# CAPT-B1-01_Cap_Touch_Matrix_Shield.net
KiCad netlist of a schematic drawn in EAGLE
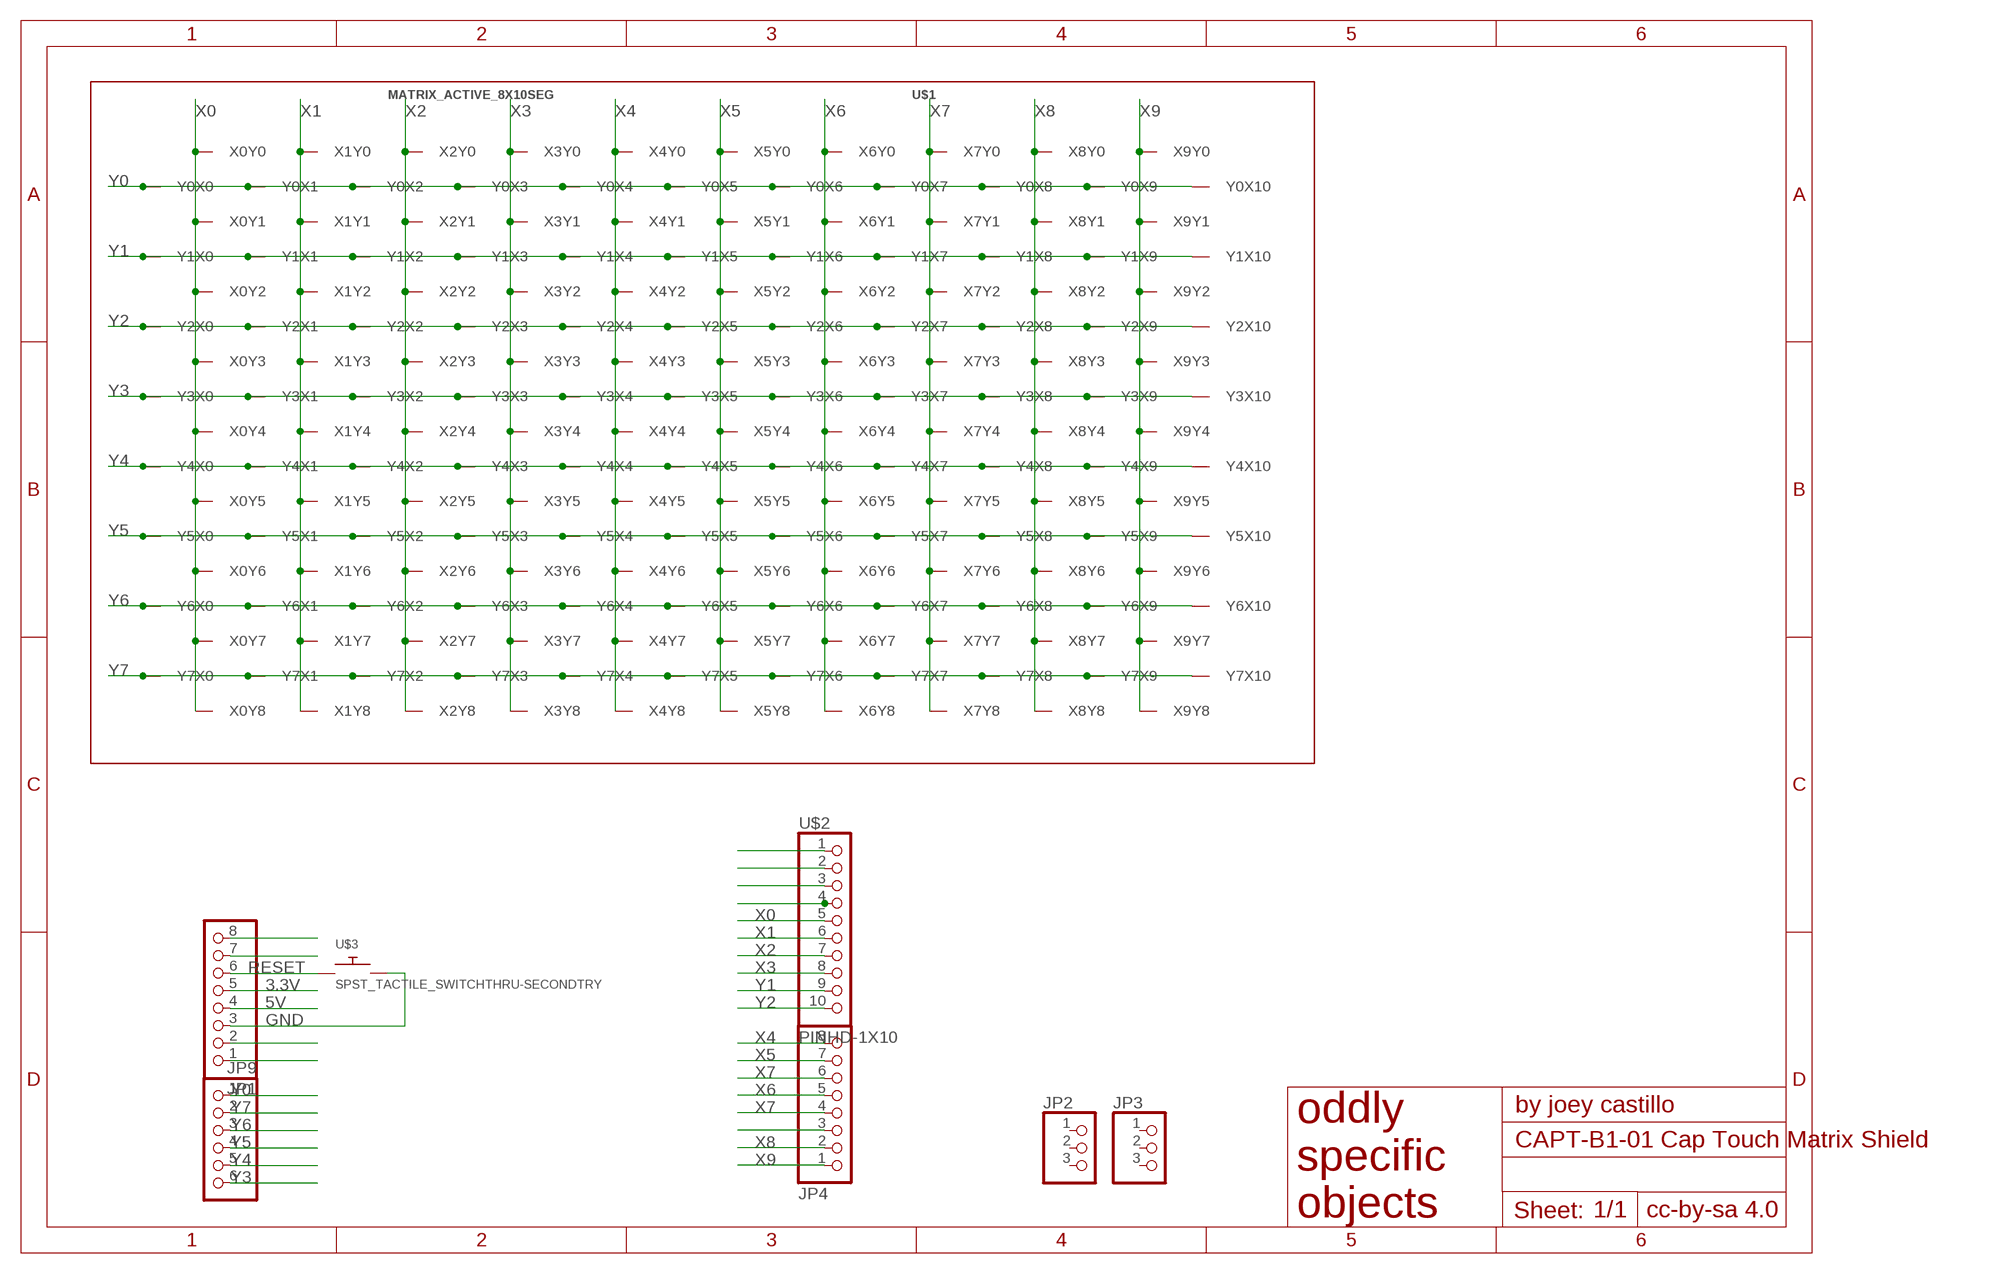
[diagram p0: schematic, sheet 1]

(export (version "E")
  (design (tool "Eeschema 10.0.6"))
  (components
    (comp (ref "JP1")
      (value "PINHD-1X8CLEANBIG")
      (footprint "eagle-import:1X08-CLEANBIG")
      (libsource (lib "eagle-import") (part "PINHD-1X8CLEANBIG"))
    )
    (comp (ref "JP2")
      (value "PINHD-1X3CB")
      (footprint "eagle-import:1X03-CLEANBIG")
      (libsource (lib "eagle-import") (part "PINHD-1X3CB"))
    )
    (comp (ref "JP3")
      (value "PINHD-1X3CB")
      (footprint "eagle-import:1X03-CLEANBIG")
      (libsource (lib "eagle-import") (part "PINHD-1X3CB"))
    )
    (comp (ref "JP4")
      (value "PINHD-1X8CLEANBIG")
      (footprint "eagle-import:1X08-CLEANBIG")
      (libsource (lib "eagle-import") (part "PINHD-1X8CLEANBIG"))
    )
    (comp (ref "JP9")
      (value "PINHD-1X6CB")
      (footprint "eagle-import:1X06-CLEANBIG")
      (libsource (lib "eagle-import") (part "PINHD-1X6CB"))
    )
    (comp (ref "U$1")
      (value "MATRIX_ACTIVE_8X10SEG")
      (footprint "eagle-import:MATRIX_ACTIVE_8X10SEG_4MM")
      (libsource (lib "eagle-import") (part "MATRIX_ACTIVE_8X10SEG"))
    )
    (comp (ref "U$2")
      (value "PINHD-1X10")
      (footprint "eagle-import:1X10-BIG")
      (libsource (lib "eagle-import") (part "PINHD-1X10"))
    )
    (comp (ref "U$3")
      (value "SPST_TACTILE_SWITCHTHRU-SECONDTRY")
      (footprint "eagle-import:MJTP1250-TRY2")
      (libsource (lib "eagle-import") (part "SPST_TACTILE_SWITCHTHRU-SECONDTRY"))
    )
  )
  (nets
    (net (code "1") (name "/3.3V") (class "Default")
      (node (ref "JP1") (pin "5") (pinfunction "5_5") (pintype "passive"))
    )
    (net (code "2") (name "/5V") (class "Default")
      (node (ref "JP1") (pin "4") (pinfunction "4_4") (pintype "passive"))
    )
    (net (code "3") (name "/GND") (class "Default")
      (node (ref "JP1") (pin "3") (pinfunction "3_3") (pintype "passive"))
      (node (ref "U$3") (pin "P$2") (pinfunction "P$2_P$2") (pintype "passive"))
    )
    (net (code "4") (name "/RESET") (class "Default")
      (node (ref "JP1") (pin "6") (pinfunction "6_6") (pintype "passive"))
      (node (ref "U$3") (pin "P$1") (pinfunction "P$1_P$1") (pintype "passive"))
    )
    (net (code "5") (name "/X0") (class "Default")
      (node (ref "U$1") (pin "X0Y0") (pinfunction "X0Y0_X0Y0") (pintype "passive"))
      (node (ref "U$1") (pin "X0Y1") (pinfunction "X0Y1_X0Y1") (pintype "passive"))
      (node (ref "U$1") (pin "X0Y2") (pinfunction "X0Y2_X0Y2") (pintype "passive"))
      (node (ref "U$1") (pin "X0Y3") (pinfunction "X0Y3_X0Y3") (pintype "passive"))
      (node (ref "U$1") (pin "X0Y4") (pinfunction "X0Y4_X0Y4") (pintype "passive"))
      (node (ref "U$1") (pin "X0Y5") (pinfunction "X0Y5_X0Y5") (pintype "passive"))
      (node (ref "U$1") (pin "X0Y6") (pinfunction "X0Y6_X0Y6") (pintype "passive"))
      (node (ref "U$1") (pin "X0Y7") (pinfunction "X0Y7_X0Y7") (pintype "passive"))
      (node (ref "U$1") (pin "X0Y8") (pinfunction "X0Y8_X0Y8") (pintype "passive"))
      (node (ref "U$2") (pin "5") (pinfunction "5_5") (pintype "passive"))
    )
    (net (code "6") (name "/X1") (class "Default")
      (node (ref "U$1") (pin "X1Y0") (pinfunction "X1Y0_X1Y0") (pintype "passive"))
      (node (ref "U$1") (pin "X1Y1") (pinfunction "X1Y1_X1Y1") (pintype "passive"))
      (node (ref "U$1") (pin "X1Y2") (pinfunction "X1Y2_X1Y2") (pintype "passive"))
      (node (ref "U$1") (pin "X1Y3") (pinfunction "X1Y3_X1Y3") (pintype "passive"))
      (node (ref "U$1") (pin "X1Y4") (pinfunction "X1Y4_X1Y4") (pintype "passive"))
      (node (ref "U$1") (pin "X1Y5") (pinfunction "X1Y5_X1Y5") (pintype "passive"))
      (node (ref "U$1") (pin "X1Y6") (pinfunction "X1Y6_X1Y6") (pintype "passive"))
      (node (ref "U$1") (pin "X1Y7") (pinfunction "X1Y7_X1Y7") (pintype "passive"))
      (node (ref "U$1") (pin "X1Y8") (pinfunction "X1Y8_X1Y8") (pintype "passive"))
      (node (ref "U$2") (pin "6") (pinfunction "6_6") (pintype "passive"))
    )
    (net (code "7") (name "/X2") (class "Default")
      (node (ref "U$1") (pin "X2Y0") (pinfunction "X2Y0_X2Y0") (pintype "passive"))
      (node (ref "U$1") (pin "X2Y1") (pinfunction "X2Y1_X2Y1") (pintype "passive"))
      (node (ref "U$1") (pin "X2Y2") (pinfunction "X2Y2_X2Y2") (pintype "passive"))
      (node (ref "U$1") (pin "X2Y3") (pinfunction "X2Y3_X2Y3") (pintype "passive"))
      (node (ref "U$1") (pin "X2Y4") (pinfunction "X2Y4_X2Y4") (pintype "passive"))
      (node (ref "U$1") (pin "X2Y5") (pinfunction "X2Y5_X2Y5") (pintype "passive"))
      (node (ref "U$1") (pin "X2Y6") (pinfunction "X2Y6_X2Y6") (pintype "passive"))
      (node (ref "U$1") (pin "X2Y7") (pinfunction "X2Y7_X2Y7") (pintype "passive"))
      (node (ref "U$1") (pin "X2Y8") (pinfunction "X2Y8_X2Y8") (pintype "passive"))
      (node (ref "U$2") (pin "7") (pinfunction "7_7") (pintype "passive"))
    )
    (net (code "8") (name "/X3") (class "Default")
      (node (ref "U$1") (pin "X3Y0") (pinfunction "X3Y0_X3Y0") (pintype "passive"))
      (node (ref "U$1") (pin "X3Y1") (pinfunction "X3Y1_X3Y1") (pintype "passive"))
      (node (ref "U$1") (pin "X3Y2") (pinfunction "X3Y2_X3Y2") (pintype "passive"))
      (node (ref "U$1") (pin "X3Y3") (pinfunction "X3Y3_X3Y3") (pintype "passive"))
      (node (ref "U$1") (pin "X3Y4") (pinfunction "X3Y4_X3Y4") (pintype "passive"))
      (node (ref "U$1") (pin "X3Y5") (pinfunction "X3Y5_X3Y5") (pintype "passive"))
      (node (ref "U$1") (pin "X3Y6") (pinfunction "X3Y6_X3Y6") (pintype "passive"))
      (node (ref "U$1") (pin "X3Y7") (pinfunction "X3Y7_X3Y7") (pintype "passive"))
      (node (ref "U$1") (pin "X3Y8") (pinfunction "X3Y8_X3Y8") (pintype "passive"))
      (node (ref "U$2") (pin "8") (pinfunction "8_8") (pintype "passive"))
    )
    (net (code "9") (name "/X4") (class "Default")
      (node (ref "JP4") (pin "8") (pinfunction "8_8") (pintype "passive"))
      (node (ref "U$1") (pin "X4Y0") (pinfunction "X4Y0_X4Y0") (pintype "passive"))
      (node (ref "U$1") (pin "X4Y1") (pinfunction "X4Y1_X4Y1") (pintype "passive"))
      (node (ref "U$1") (pin "X4Y2") (pinfunction "X4Y2_X4Y2") (pintype "passive"))
      (node (ref "U$1") (pin "X4Y3") (pinfunction "X4Y3_X4Y3") (pintype "passive"))
      (node (ref "U$1") (pin "X4Y4") (pinfunction "X4Y4_X4Y4") (pintype "passive"))
      (node (ref "U$1") (pin "X4Y5") (pinfunction "X4Y5_X4Y5") (pintype "passive"))
      (node (ref "U$1") (pin "X4Y6") (pinfunction "X4Y6_X4Y6") (pintype "passive"))
      (node (ref "U$1") (pin "X4Y7") (pinfunction "X4Y7_X4Y7") (pintype "passive"))
      (node (ref "U$1") (pin "X4Y8") (pinfunction "X4Y8_X4Y8") (pintype "passive"))
    )
    (net (code "10") (name "/X5") (class "Default")
      (node (ref "JP4") (pin "7") (pinfunction "7_7") (pintype "passive"))
      (node (ref "U$1") (pin "X5Y0") (pinfunction "X5Y0_X5Y0") (pintype "passive"))
      (node (ref "U$1") (pin "X5Y1") (pinfunction "X5Y1_X5Y1") (pintype "passive"))
      (node (ref "U$1") (pin "X5Y2") (pinfunction "X5Y2_X5Y2") (pintype "passive"))
      (node (ref "U$1") (pin "X5Y3") (pinfunction "X5Y3_X5Y3") (pintype "passive"))
      (node (ref "U$1") (pin "X5Y4") (pinfunction "X5Y4_X5Y4") (pintype "passive"))
      (node (ref "U$1") (pin "X5Y5") (pinfunction "X5Y5_X5Y5") (pintype "passive"))
      (node (ref "U$1") (pin "X5Y6") (pinfunction "X5Y6_X5Y6") (pintype "passive"))
      (node (ref "U$1") (pin "X5Y7") (pinfunction "X5Y7_X5Y7") (pintype "passive"))
      (node (ref "U$1") (pin "X5Y8") (pinfunction "X5Y8_X5Y8") (pintype "passive"))
    )
    (net (code "11") (name "/X6") (class "Default")
      (node (ref "JP4") (pin "5") (pinfunction "5_5") (pintype "passive"))
      (node (ref "U$1") (pin "X6Y0") (pinfunction "X6Y0_X6Y0") (pintype "passive"))
      (node (ref "U$1") (pin "X6Y1") (pinfunction "X6Y1_X6Y1") (pintype "passive"))
      (node (ref "U$1") (pin "X6Y2") (pinfunction "X6Y2_X6Y2") (pintype "passive"))
      (node (ref "U$1") (pin "X6Y3") (pinfunction "X6Y3_X6Y3") (pintype "passive"))
      (node (ref "U$1") (pin "X6Y4") (pinfunction "X6Y4_X6Y4") (pintype "passive"))
      (node (ref "U$1") (pin "X6Y5") (pinfunction "X6Y5_X6Y5") (pintype "passive"))
      (node (ref "U$1") (pin "X6Y6") (pinfunction "X6Y6_X6Y6") (pintype "passive"))
      (node (ref "U$1") (pin "X6Y7") (pinfunction "X6Y7_X6Y7") (pintype "passive"))
      (node (ref "U$1") (pin "X6Y8") (pinfunction "X6Y8_X6Y8") (pintype "passive"))
    )
    (net (code "12") (name "/X7") (class "Default")
      (node (ref "JP4") (pin "4") (pinfunction "4_4") (pintype "passive"))
      (node (ref "JP4") (pin "6") (pinfunction "6_6") (pintype "passive"))
      (node (ref "U$1") (pin "X7Y0") (pinfunction "X7Y0_X7Y0") (pintype "passive"))
      (node (ref "U$1") (pin "X7Y1") (pinfunction "X7Y1_X7Y1") (pintype "passive"))
      (node (ref "U$1") (pin "X7Y2") (pinfunction "X7Y2_X7Y2") (pintype "passive"))
      (node (ref "U$1") (pin "X7Y3") (pinfunction "X7Y3_X7Y3") (pintype "passive"))
      (node (ref "U$1") (pin "X7Y4") (pinfunction "X7Y4_X7Y4") (pintype "passive"))
      (node (ref "U$1") (pin "X7Y5") (pinfunction "X7Y5_X7Y5") (pintype "passive"))
      (node (ref "U$1") (pin "X7Y6") (pinfunction "X7Y6_X7Y6") (pintype "passive"))
      (node (ref "U$1") (pin "X7Y7") (pinfunction "X7Y7_X7Y7") (pintype "passive"))
      (node (ref "U$1") (pin "X7Y8") (pinfunction "X7Y8_X7Y8") (pintype "passive"))
    )
    (net (code "13") (name "/X8") (class "Default")
      (node (ref "JP4") (pin "2") (pinfunction "2_2") (pintype "passive"))
      (node (ref "U$1") (pin "X8Y0") (pinfunction "X8Y0_X8Y0") (pintype "passive"))
      (node (ref "U$1") (pin "X8Y1") (pinfunction "X8Y1_X8Y1") (pintype "passive"))
      (node (ref "U$1") (pin "X8Y2") (pinfunction "X8Y2_X8Y2") (pintype "passive"))
      (node (ref "U$1") (pin "X8Y3") (pinfunction "X8Y3_X8Y3") (pintype "passive"))
      (node (ref "U$1") (pin "X8Y4") (pinfunction "X8Y4_X8Y4") (pintype "passive"))
      (node (ref "U$1") (pin "X8Y5") (pinfunction "X8Y5_X8Y5") (pintype "passive"))
      (node (ref "U$1") (pin "X8Y6") (pinfunction "X8Y6_X8Y6") (pintype "passive"))
      (node (ref "U$1") (pin "X8Y7") (pinfunction "X8Y7_X8Y7") (pintype "passive"))
      (node (ref "U$1") (pin "X8Y8") (pinfunction "X8Y8_X8Y8") (pintype "passive"))
    )
    (net (code "14") (name "/X9") (class "Default")
      (node (ref "JP4") (pin "1") (pinfunction "1_1") (pintype "passive"))
      (node (ref "U$1") (pin "X9Y0") (pinfunction "X9Y0_X9Y0") (pintype "passive"))
      (node (ref "U$1") (pin "X9Y1") (pinfunction "X9Y1_X9Y1") (pintype "passive"))
      (node (ref "U$1") (pin "X9Y2") (pinfunction "X9Y2_X9Y2") (pintype "passive"))
      (node (ref "U$1") (pin "X9Y3") (pinfunction "X9Y3_X9Y3") (pintype "passive"))
      (node (ref "U$1") (pin "X9Y4") (pinfunction "X9Y4_X9Y4") (pintype "passive"))
      (node (ref "U$1") (pin "X9Y5") (pinfunction "X9Y5_X9Y5") (pintype "passive"))
      (node (ref "U$1") (pin "X9Y6") (pinfunction "X9Y6_X9Y6") (pintype "passive"))
      (node (ref "U$1") (pin "X9Y7") (pinfunction "X9Y7_X9Y7") (pintype "passive"))
      (node (ref "U$1") (pin "X9Y8") (pinfunction "X9Y8_X9Y8") (pintype "passive"))
    )
    (net (code "15") (name "/Y0") (class "Default")
      (node (ref "JP9") (pin "1") (pinfunction "1_1") (pintype "passive"))
      (node (ref "U$1") (pin "Y0X0") (pinfunction "Y0X0_Y0X0") (pintype "passive"))
      (node (ref "U$1") (pin "Y0X1") (pinfunction "Y0X1_Y0X1") (pintype "passive"))
      (node (ref "U$1") (pin "Y0X10") (pinfunction "Y0X10_Y0X10") (pintype "passive"))
      (node (ref "U$1") (pin "Y0X2") (pinfunction "Y0X2_Y0X2") (pintype "passive"))
      (node (ref "U$1") (pin "Y0X3") (pinfunction "Y0X3_Y0X3") (pintype "passive"))
      (node (ref "U$1") (pin "Y0X4") (pinfunction "Y0X4_Y0X4") (pintype "passive"))
      (node (ref "U$1") (pin "Y0X5") (pinfunction "Y0X5_Y0X5") (pintype "passive"))
      (node (ref "U$1") (pin "Y0X6") (pinfunction "Y0X6_Y0X6") (pintype "passive"))
      (node (ref "U$1") (pin "Y0X7") (pinfunction "Y0X7_Y0X7") (pintype "passive"))
      (node (ref "U$1") (pin "Y0X8") (pinfunction "Y0X8_Y0X8") (pintype "passive"))
      (node (ref "U$1") (pin "Y0X9") (pinfunction "Y0X9_Y0X9") (pintype "passive"))
    )
    (net (code "16") (name "/Y1") (class "Default")
      (node (ref "U$1") (pin "Y1X0") (pinfunction "Y1X0_Y1X0") (pintype "passive"))
      (node (ref "U$1") (pin "Y1X1") (pinfunction "Y1X1_Y1X1") (pintype "passive"))
      (node (ref "U$1") (pin "Y1X10") (pinfunction "Y1X10_Y1X10") (pintype "passive"))
      (node (ref "U$1") (pin "Y1X2") (pinfunction "Y1X2_Y1X2") (pintype "passive"))
      (node (ref "U$1") (pin "Y1X3") (pinfunction "Y1X3_Y1X3") (pintype "passive"))
      (node (ref "U$1") (pin "Y1X4") (pinfunction "Y1X4_Y1X4") (pintype "passive"))
      (node (ref "U$1") (pin "Y1X5") (pinfunction "Y1X5_Y1X5") (pintype "passive"))
      (node (ref "U$1") (pin "Y1X6") (pinfunction "Y1X6_Y1X6") (pintype "passive"))
      (node (ref "U$1") (pin "Y1X7") (pinfunction "Y1X7_Y1X7") (pintype "passive"))
      (node (ref "U$1") (pin "Y1X8") (pinfunction "Y1X8_Y1X8") (pintype "passive"))
      (node (ref "U$1") (pin "Y1X9") (pinfunction "Y1X9_Y1X9") (pintype "passive"))
      (node (ref "U$2") (pin "9") (pinfunction "9_9") (pintype "passive"))
    )
    (net (code "17") (name "/Y2") (class "Default")
      (node (ref "U$1") (pin "Y2X0") (pinfunction "Y2X0_Y2X0") (pintype "passive"))
      (node (ref "U$1") (pin "Y2X1") (pinfunction "Y2X1_Y2X1") (pintype "passive"))
      (node (ref "U$1") (pin "Y2X10") (pinfunction "Y2X10_Y2X10") (pintype "passive"))
      (node (ref "U$1") (pin "Y2X2") (pinfunction "Y2X2_Y2X2") (pintype "passive"))
      (node (ref "U$1") (pin "Y2X3") (pinfunction "Y2X3_Y2X3") (pintype "passive"))
      (node (ref "U$1") (pin "Y2X4") (pinfunction "Y2X4_Y2X4") (pintype "passive"))
      (node (ref "U$1") (pin "Y2X5") (pinfunction "Y2X5_Y2X5") (pintype "passive"))
      (node (ref "U$1") (pin "Y2X6") (pinfunction "Y2X6_Y2X6") (pintype "passive"))
      (node (ref "U$1") (pin "Y2X7") (pinfunction "Y2X7_Y2X7") (pintype "passive"))
      (node (ref "U$1") (pin "Y2X8") (pinfunction "Y2X8_Y2X8") (pintype "passive"))
      (node (ref "U$1") (pin "Y2X9") (pinfunction "Y2X9_Y2X9") (pintype "passive"))
      (node (ref "U$2") (pin "10") (pinfunction "10_10") (pintype "passive"))
    )
    (net (code "18") (name "/Y3") (class "Default")
      (node (ref "JP9") (pin "6") (pinfunction "6_6") (pintype "passive"))
      (node (ref "U$1") (pin "Y3X0") (pinfunction "Y3X0_Y3X0") (pintype "passive"))
      (node (ref "U$1") (pin "Y3X1") (pinfunction "Y3X1_Y3X1") (pintype "passive"))
      (node (ref "U$1") (pin "Y3X10") (pinfunction "Y3X10_Y3X10") (pintype "passive"))
      (node (ref "U$1") (pin "Y3X2") (pinfunction "Y3X2_Y3X2") (pintype "passive"))
      (node (ref "U$1") (pin "Y3X3") (pinfunction "Y3X3_Y3X3") (pintype "passive"))
      (node (ref "U$1") (pin "Y3X4") (pinfunction "Y3X4_Y3X4") (pintype "passive"))
      (node (ref "U$1") (pin "Y3X5") (pinfunction "Y3X5_Y3X5") (pintype "passive"))
      (node (ref "U$1") (pin "Y3X6") (pinfunction "Y3X6_Y3X6") (pintype "passive"))
      (node (ref "U$1") (pin "Y3X7") (pinfunction "Y3X7_Y3X7") (pintype "passive"))
      (node (ref "U$1") (pin "Y3X8") (pinfunction "Y3X8_Y3X8") (pintype "passive"))
      (node (ref "U$1") (pin "Y3X9") (pinfunction "Y3X9_Y3X9") (pintype "passive"))
    )
    (net (code "19") (name "/Y4") (class "Default")
      (node (ref "JP9") (pin "5") (pinfunction "5_5") (pintype "passive"))
      (node (ref "U$1") (pin "Y4X0") (pinfunction "Y4X0_Y4X0") (pintype "passive"))
      (node (ref "U$1") (pin "Y4X1") (pinfunction "Y4X1_Y4X1") (pintype "passive"))
      (node (ref "U$1") (pin "Y4X10") (pinfunction "Y4X10_Y4X10") (pintype "passive"))
      (node (ref "U$1") (pin "Y4X2") (pinfunction "Y4X2_Y4X2") (pintype "passive"))
      (node (ref "U$1") (pin "Y4X3") (pinfunction "Y4X3_Y4X3") (pintype "passive"))
      (node (ref "U$1") (pin "Y4X4") (pinfunction "Y4X4_Y4X4") (pintype "passive"))
      (node (ref "U$1") (pin "Y4X5") (pinfunction "Y4X5_Y4X5") (pintype "passive"))
      (node (ref "U$1") (pin "Y4X6") (pinfunction "Y4X6_Y4X6") (pintype "passive"))
      (node (ref "U$1") (pin "Y4X7") (pinfunction "Y4X7_Y4X7") (pintype "passive"))
      (node (ref "U$1") (pin "Y4X8") (pinfunction "Y4X8_Y4X8") (pintype "passive"))
      (node (ref "U$1") (pin "Y4X9") (pinfunction "Y4X9_Y4X9") (pintype "passive"))
    )
    (net (code "20") (name "/Y5") (class "Default")
      (node (ref "JP9") (pin "4") (pinfunction "4_4") (pintype "passive"))
      (node (ref "U$1") (pin "Y5X0") (pinfunction "Y5X0_Y5X0") (pintype "passive"))
      (node (ref "U$1") (pin "Y5X1") (pinfunction "Y5X1_Y5X1") (pintype "passive"))
      (node (ref "U$1") (pin "Y5X10") (pinfunction "Y5X10_Y5X10") (pintype "passive"))
      (node (ref "U$1") (pin "Y5X2") (pinfunction "Y5X2_Y5X2") (pintype "passive"))
      (node (ref "U$1") (pin "Y5X3") (pinfunction "Y5X3_Y5X3") (pintype "passive"))
      (node (ref "U$1") (pin "Y5X4") (pinfunction "Y5X4_Y5X4") (pintype "passive"))
      (node (ref "U$1") (pin "Y5X5") (pinfunction "Y5X5_Y5X5") (pintype "passive"))
      (node (ref "U$1") (pin "Y5X6") (pinfunction "Y5X6_Y5X6") (pintype "passive"))
      (node (ref "U$1") (pin "Y5X7") (pinfunction "Y5X7_Y5X7") (pintype "passive"))
      (node (ref "U$1") (pin "Y5X8") (pinfunction "Y5X8_Y5X8") (pintype "passive"))
      (node (ref "U$1") (pin "Y5X9") (pinfunction "Y5X9_Y5X9") (pintype "passive"))
    )
    (net (code "21") (name "/Y6") (class "Default")
      (node (ref "JP9") (pin "3") (pinfunction "3_3") (pintype "passive"))
      (node (ref "U$1") (pin "Y6X0") (pinfunction "Y6X0_Y6X0") (pintype "passive"))
      (node (ref "U$1") (pin "Y6X1") (pinfunction "Y6X1_Y6X1") (pintype "passive"))
      (node (ref "U$1") (pin "Y6X10") (pinfunction "Y6X10_Y6X10") (pintype "passive"))
      (node (ref "U$1") (pin "Y6X2") (pinfunction "Y6X2_Y6X2") (pintype "passive"))
      (node (ref "U$1") (pin "Y6X3") (pinfunction "Y6X3_Y6X3") (pintype "passive"))
      (node (ref "U$1") (pin "Y6X4") (pinfunction "Y6X4_Y6X4") (pintype "passive"))
      (node (ref "U$1") (pin "Y6X5") (pinfunction "Y6X5_Y6X5") (pintype "passive"))
      (node (ref "U$1") (pin "Y6X6") (pinfunction "Y6X6_Y6X6") (pintype "passive"))
      (node (ref "U$1") (pin "Y6X7") (pinfunction "Y6X7_Y6X7") (pintype "passive"))
      (node (ref "U$1") (pin "Y6X8") (pinfunction "Y6X8_Y6X8") (pintype "passive"))
      (node (ref "U$1") (pin "Y6X9") (pinfunction "Y6X9_Y6X9") (pintype "passive"))
    )
    (net (code "22") (name "/Y7") (class "Default")
      (node (ref "JP9") (pin "2") (pinfunction "2_2") (pintype "passive"))
      (node (ref "U$1") (pin "Y7X0") (pinfunction "Y7X0_Y7X0") (pintype "passive"))
      (node (ref "U$1") (pin "Y7X1") (pinfunction "Y7X1_Y7X1") (pintype "passive"))
      (node (ref "U$1") (pin "Y7X10") (pinfunction "Y7X10_Y7X10") (pintype "passive"))
      (node (ref "U$1") (pin "Y7X2") (pinfunction "Y7X2_Y7X2") (pintype "passive"))
      (node (ref "U$1") (pin "Y7X3") (pinfunction "Y7X3_Y7X3") (pintype "passive"))
      (node (ref "U$1") (pin "Y7X4") (pinfunction "Y7X4_Y7X4") (pintype "passive"))
      (node (ref "U$1") (pin "Y7X5") (pinfunction "Y7X5_Y7X5") (pintype "passive"))
      (node (ref "U$1") (pin "Y7X6") (pinfunction "Y7X6_Y7X6") (pintype "passive"))
      (node (ref "U$1") (pin "Y7X7") (pinfunction "Y7X7_Y7X7") (pintype "passive"))
      (node (ref "U$1") (pin "Y7X8") (pinfunction "Y7X8_Y7X8") (pintype "passive"))
      (node (ref "U$1") (pin "Y7X9") (pinfunction "Y7X9_Y7X9") (pintype "passive"))
    )
    (net (code "23") (name "unconnected-(JP1-Pad1)") (class "Default")
      (node (ref "JP1") (pin "1") (pinfunction "1_1") (pintype "passive"))
    )
    (net (code "24") (name "unconnected-(JP1-Pad2)") (class "Default")
      (node (ref "JP1") (pin "2") (pinfunction "2_2") (pintype "passive"))
    )
    (net (code "25") (name "unconnected-(JP1-Pad7)") (class "Default")
      (node (ref "JP1") (pin "7") (pinfunction "7_7") (pintype "passive"))
    )
    (net (code "26") (name "unconnected-(JP1-Pad8)") (class "Default")
      (node (ref "JP1") (pin "8") (pinfunction "8_8") (pintype "passive"))
    )
    (net (code "27") (name "unconnected-(JP2-Pad1)") (class "Default")
      (node (ref "JP2") (pin "1") (pinfunction "1_1") (pintype "passive"))
    )
    (net (code "28") (name "unconnected-(JP2-Pad2)") (class "Default")
      (node (ref "JP2") (pin "2") (pinfunction "2_2") (pintype "passive"))
    )
    (net (code "29") (name "unconnected-(JP2-Pad3)") (class "Default")
      (node (ref "JP2") (pin "3") (pinfunction "3_3") (pintype "passive"))
    )
    (net (code "30") (name "unconnected-(JP3-Pad1)") (class "Default")
      (node (ref "JP3") (pin "1") (pinfunction "1_1") (pintype "passive"))
    )
    (net (code "31") (name "unconnected-(JP3-Pad2)") (class "Default")
      (node (ref "JP3") (pin "2") (pinfunction "2_2") (pintype "passive"))
    )
    (net (code "32") (name "unconnected-(JP3-Pad3)") (class "Default")
      (node (ref "JP3") (pin "3") (pinfunction "3_3") (pintype "passive"))
    )
    (net (code "33") (name "unconnected-(JP4-Pad3)") (class "Default")
      (node (ref "JP4") (pin "3") (pinfunction "3_3") (pintype "passive"))
    )
    (net (code "34") (name "unconnected-(U$2-Pad1)") (class "Default")
      (node (ref "U$2") (pin "1") (pinfunction "1_1") (pintype "passive"))
    )
    (net (code "35") (name "unconnected-(U$2-Pad2)") (class "Default")
      (node (ref "U$2") (pin "2") (pinfunction "2_2") (pintype "passive"))
    )
    (net (code "36") (name "unconnected-(U$2-Pad3)") (class "Default")
      (node (ref "U$2") (pin "3") (pinfunction "3_3") (pintype "passive"))
    )
    (net (code "37") (name "unconnected-(U$2-Pad4)") (class "Default")
      (node (ref "U$2") (pin "4") (pinfunction "4_4") (pintype "passive"))
    )
  )
)
